# PI_R3_REV1_LCD.net
KiCad netlist of a schematic drawn in Altium Designer
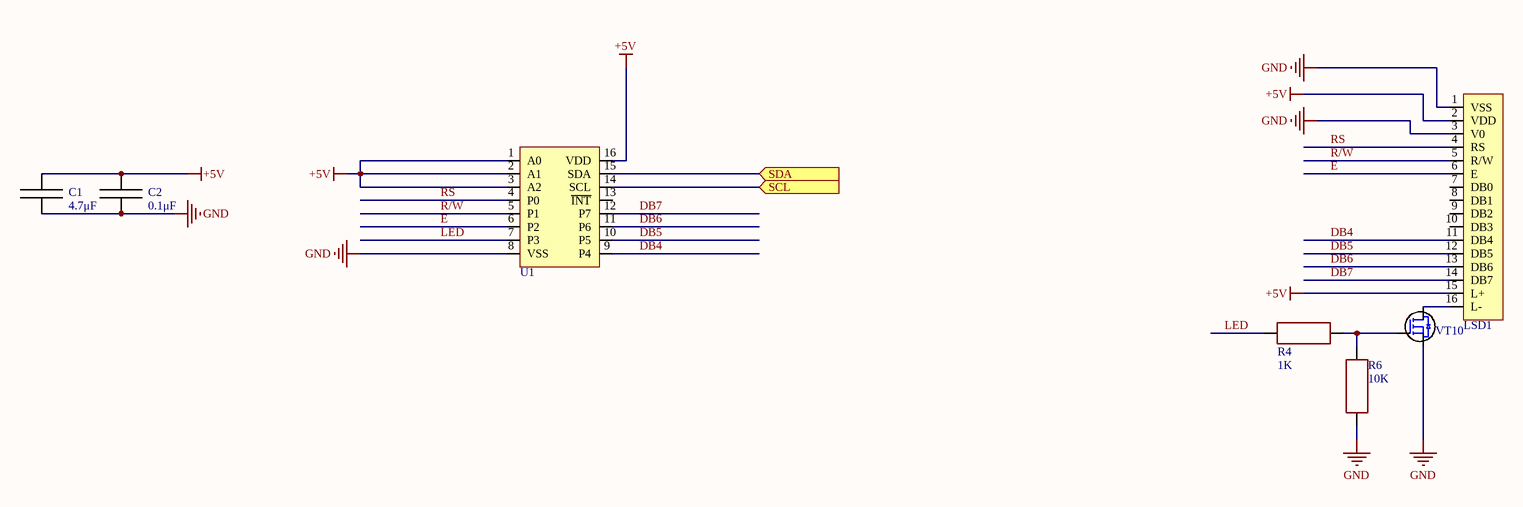
[diagram p0: PI_R3_REV1_LCD.SchDoc]

(export (version "E")
  (design (tool "Eeschema 10.0.6"))
  (components
    (comp (ref "C1")
      (value "4.7μF")
      (footprint "CAP: 0402")
      (fields (field (name "VOLTAGE") "??V") (field (name "Comment") "Cap_0402"))
      (libsource (lib "capacitor") (part "Cap_0402"))
    )
    (comp (ref "C2")
      (value "0.1μF")
      (footprint "CAP: 0402")
      (fields (field (name "VOLTAGE") "??V") (field (name "Comment") "Cap_0402"))
      (libsource (lib "capacitor") (part "Cap_0402"))
    )
    (comp (ref "LSD1")
      (value "WH2004A")
      (footprint "WH2004A")
      (description "LCD Character Display  20x4")
      (fields (field (name "MANUFACTURER") "Winstar"))
      (libsource (lib "MY_INT_LIB") (part "WH2004A"))
    )
    (comp (ref "R4")
      (value "1K")
      (footprint "RES: 0402")
      (fields (field (name "TOLERANCE") "±5%"))
      (libsource (lib "resistor") (part "Resistor_0402"))
    )
    (comp (ref "R6")
      (value "10K")
      (footprint "RES: 0402")
      (fields (field (name "TOLERANCE") "±5%"))
      (libsource (lib "") (part "Resistor_0402_1"))
    )
    (comp (ref "U1")
      (value "PCF8574")
      (footprint "SOIC-16")
      (description "1 MHz, Low-Power Op Amp")
      (fields (field (name "MANUFACTURER") "NXP"))
      (libsource (lib "MY_INT_LIB") (part "PCF8574"))
    )
    (comp (ref "VT10")
      (value "2N7002(NX7002AK)")
      (footprint "SOT-23-3")
      (description "MOSFET N-CHANNEL 60V 115mA")
      (fields (field (name "MANUFACTURER") "Fairchild"))
      (libsource (lib "MY_INT_LIB") (part "2N7002"))
    )
  )
  (nets
    (net (code "1") (name "+5V") (class "Default")
      (node (ref "C1") (pin "2") (pinfunction "2_2") (pintype "passive"))
      (node (ref "C2") (pin "2") (pinfunction "2_2") (pintype "passive"))
      (node (ref "LSD1") (pin "15") (pinfunction "L+_15") (pintype "passive"))
      (node (ref "LSD1") (pin "2") (pinfunction "VDD_2") (pintype "power_in"))
      (node (ref "U1") (pin "1") (pinfunction "A0_1") (pintype "passive"))
      (node (ref "U1") (pin "16") (pinfunction "VDD_16") (pintype "passive"))
      (node (ref "U1") (pin "2") (pinfunction "A1_2") (pintype "passive"))
      (node (ref "U1") (pin "3") (pinfunction "A2_3") (pintype "passive"))
    )
    (net (code "2") (name "/DB4") (class "Default")
      (node (ref "LSD1") (pin "11") (pinfunction "DB4_11") (pintype "passive"))
      (node (ref "U1") (pin "9") (pinfunction "P4_9") (pintype "passive"))
    )
    (net (code "3") (name "/DB5") (class "Default")
      (node (ref "LSD1") (pin "12") (pinfunction "DB5_12") (pintype "passive"))
      (node (ref "U1") (pin "10") (pinfunction "P5_10") (pintype "passive"))
    )
    (net (code "4") (name "/DB6") (class "Default")
      (node (ref "LSD1") (pin "13") (pinfunction "DB6_13") (pintype "passive"))
      (node (ref "U1") (pin "11") (pinfunction "P6_11") (pintype "power_in"))
    )
    (net (code "5") (name "/DB7") (class "Default")
      (node (ref "LSD1") (pin "14") (pinfunction "DB7_14") (pintype "passive"))
      (node (ref "U1") (pin "12") (pinfunction "P7_12") (pintype "passive"))
    )
    (net (code "6") (name "/E") (class "Default")
      (node (ref "LSD1") (pin "6") (pinfunction "E_6") (pintype "passive"))
      (node (ref "U1") (pin "6") (pinfunction "P2_6") (pintype "passive"))
    )
    (net (code "7") (name "/LED") (class "Default")
      (node (ref "R4") (pin "1") (pinfunction "1_1") (pintype "passive"))
      (node (ref "U1") (pin "7") (pinfunction "P3_7") (pintype "passive"))
    )
    (net (code "8") (name "/RS") (class "Default")
      (node (ref "LSD1") (pin "4") (pinfunction "RS_4") (pintype "passive"))
      (node (ref "U1") (pin "4") (pinfunction "P0_4") (pintype "power_in"))
    )
    (net (code "9") (name "/R{slash}W") (class "Default")
      (node (ref "LSD1") (pin "5") (pinfunction "R/W_5") (pintype "passive"))
      (node (ref "U1") (pin "5") (pinfunction "P1_5") (pintype "passive"))
    )
    (net (code "10") (name "/SCL") (class "Default")
      (node (ref "U1") (pin "14") (pinfunction "SCL_14") (pintype "passive"))
    )
    (net (code "11") (name "/SDA") (class "Default")
      (node (ref "U1") (pin "15") (pinfunction "SDA_15") (pintype "passive"))
    )
    (net (code "12") (name "GND") (class "Default")
      (node (ref "C1") (pin "1") (pinfunction "1_1") (pintype "passive"))
      (node (ref "C2") (pin "1") (pinfunction "1_1") (pintype "passive"))
      (node (ref "LSD1") (pin "1") (pinfunction "VSS_1") (pintype "power_in"))
      (node (ref "LSD1") (pin "3") (pinfunction "V0_3") (pintype "passive"))
      (node (ref "R6") (pin "2") (pinfunction "2_2") (pintype "passive"))
      (node (ref "U1") (pin "8") (pinfunction "VSS_8") (pintype "passive"))
      (node (ref "VT10") (pin "3") (pintype "power_in"))
    )
    (net (code "13") (name "Net-(LSD1-L-)") (class "Default")
      (node (ref "LSD1") (pin "16") (pinfunction "L-_16") (pintype "passive"))
      (node (ref "VT10") (pin "2") (pintype "power_in"))
    )
    (net (code "14") (name "Net-(R4-Pad2)") (class "Default")
      (node (ref "R4") (pin "2") (pinfunction "2_2") (pintype "passive"))
      (node (ref "R6") (pin "1") (pinfunction "1_1") (pintype "passive"))
      (node (ref "VT10") (pin "1") (pintype "power_in"))
    )
    (net (code "15") (name "unconnected-(LSD1-DB0-Pad7)") (class "Default")
      (node (ref "LSD1") (pin "7") (pinfunction "DB0_7") (pintype "passive"))
    )
    (net (code "16") (name "unconnected-(LSD1-DB1-Pad8)") (class "Default")
      (node (ref "LSD1") (pin "8") (pinfunction "DB1_8") (pintype "passive"))
    )
    (net (code "17") (name "unconnected-(LSD1-DB2-Pad9)") (class "Default")
      (node (ref "LSD1") (pin "9") (pinfunction "DB2_9") (pintype "passive"))
    )
    (net (code "18") (name "unconnected-(LSD1-DB3-Pad10)") (class "Default")
      (node (ref "LSD1") (pin "10") (pinfunction "DB3_10") (pintype "passive"))
    )
    (net (code "19") (name "unconnected-(U1-~{INT}-Pad13)") (class "Default")
      (node (ref "U1") (pin "13") (pinfunction "~{INT}_13") (pintype "passive"))
    )
  )
)
